# PotDiv1_v4.net
KiCad netlist of a schematic drawn in EAGLE
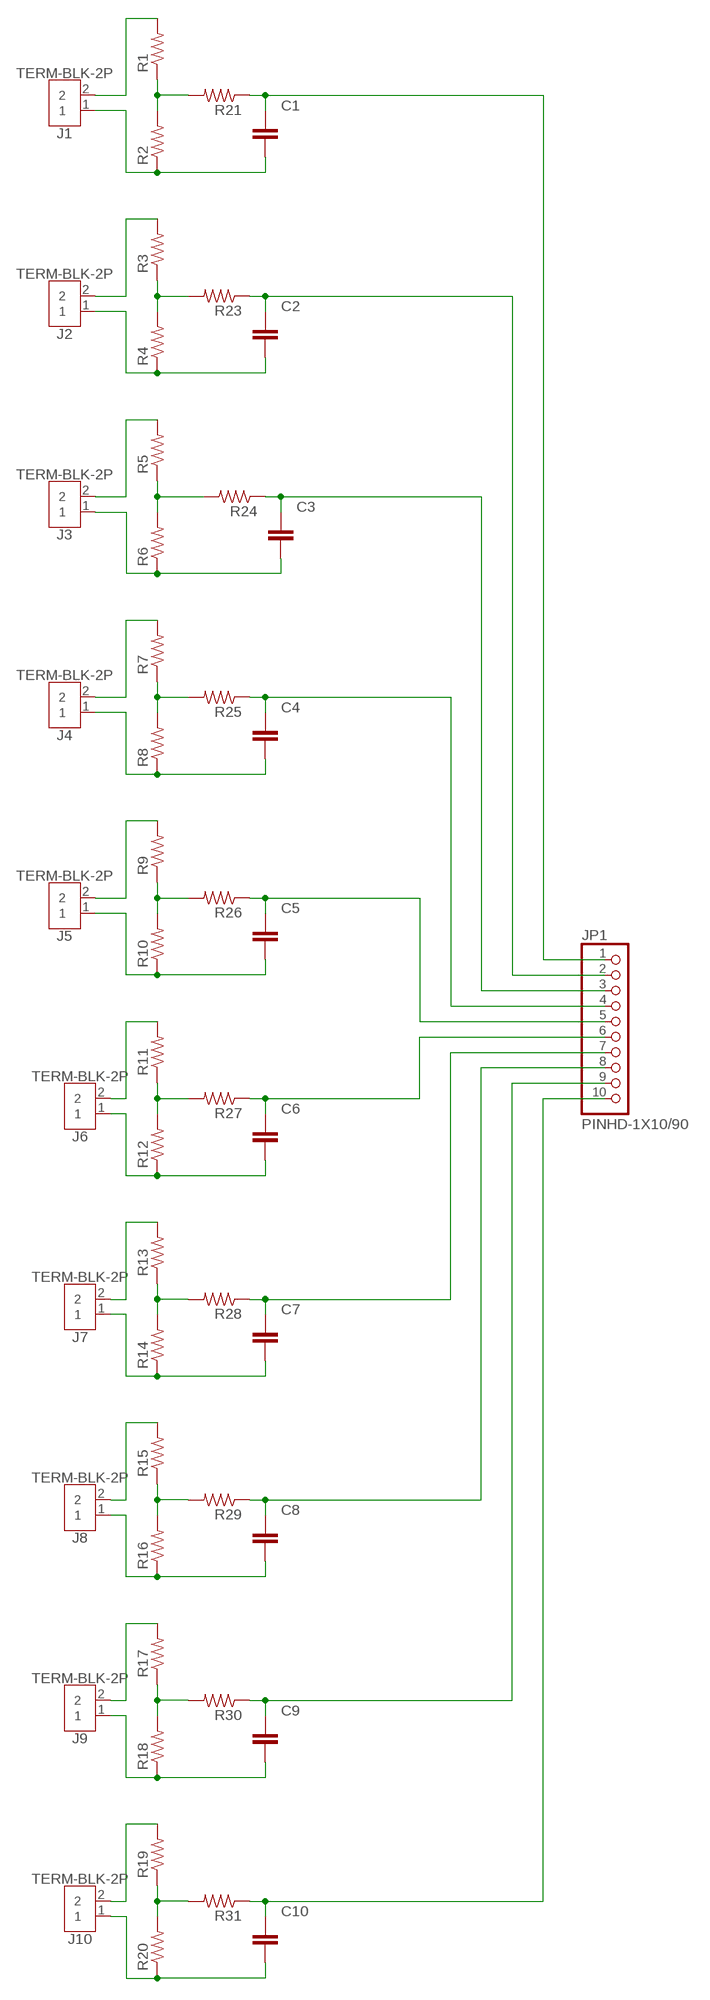
[diagram p0: schematic, sheet 1]

(export (version "E")
  (design (tool "Eeschema 10.0.6"))
  (components
    (comp (ref "C1")
      (value "C_RADIAL-12.5MM-DIA")
      (footprint "eagle-import:CAPRD550W60D1025H1250B")
      (libsource (lib "eagle-import") (part "CRADIAL-12.5MM-DIA_"))
    )
    (comp (ref "C2")
      (value "C_RADIAL-12.5MM-DIA")
      (footprint "eagle-import:CAPRD550W60D1025H1250B")
      (libsource (lib "eagle-import") (part "CRADIAL-12.5MM-DIA_"))
    )
    (comp (ref "C3")
      (value "C_RADIAL-12.5MM-DIA")
      (footprint "eagle-import:CAPRD550W60D1025H1250B")
      (libsource (lib "eagle-import") (part "CRADIAL-12.5MM-DIA_"))
    )
    (comp (ref "C4")
      (value "C_RADIAL-12.5MM-DIA")
      (footprint "eagle-import:CAPRD550W60D1025H1250B")
      (libsource (lib "eagle-import") (part "CRADIAL-12.5MM-DIA_"))
    )
    (comp (ref "C5")
      (value "C_RADIAL-12.5MM-DIA")
      (footprint "eagle-import:CAPRD550W60D1025H1250B")
      (libsource (lib "eagle-import") (part "CRADIAL-12.5MM-DIA_"))
    )
    (comp (ref "C6")
      (value "C_RADIAL-12.5MM-DIA")
      (footprint "eagle-import:CAPRD550W60D1025H1250B")
      (libsource (lib "eagle-import") (part "CRADIAL-12.5MM-DIA_"))
    )
    (comp (ref "C7")
      (value "C_RADIAL-12.5MM-DIA")
      (footprint "eagle-import:CAPRD550W60D1025H1250B")
      (libsource (lib "eagle-import") (part "CRADIAL-12.5MM-DIA_"))
    )
    (comp (ref "C8")
      (value "C_RADIAL-12.5MM-DIA")
      (footprint "eagle-import:CAPRD550W60D1025H1250B")
      (libsource (lib "eagle-import") (part "CRADIAL-12.5MM-DIA_"))
    )
    (comp (ref "C9")
      (value "C_RADIAL-12.5MM-DIA")
      (footprint "eagle-import:CAPRD550W60D1025H1250B")
      (libsource (lib "eagle-import") (part "CRADIAL-12.5MM-DIA_"))
    )
    (comp (ref "C10")
      (value "C_RADIAL-12.5MM-DIA")
      (footprint "eagle-import:CAPRD550W60D1025H1250B")
      (libsource (lib "eagle-import") (part "CRADIAL-12.5MM-DIA_"))
    )
    (comp (ref "J1")
      (value "TERM-BLK-2P")
      (footprint "eagle-import:TERMBLK_508-2N")
      (fields (field (name "MANUFACTURER") "TE Connectivity AMP Connectors") (field (name "MPN") "282837-2"))
      (libsource (lib "eagle-import") (part "2828XX-2282837-2"))
    )
    (comp (ref "J2")
      (value "TERM-BLK-2P")
      (footprint "eagle-import:TERMBLK_508-2N")
      (fields (field (name "MANUFACTURER") "TE Connectivity AMP Connectors") (field (name "MPN") "282837-2"))
      (libsource (lib "eagle-import") (part "2828XX-2282837-2"))
    )
    (comp (ref "J3")
      (value "TERM-BLK-2P")
      (footprint "eagle-import:TERMBLK_508-2N")
      (fields (field (name "MANUFACTURER") "TE Connectivity AMP Connectors") (field (name "MPN") "282837-2"))
      (libsource (lib "eagle-import") (part "2828XX-2282837-2"))
    )
    (comp (ref "J4")
      (value "TERM-BLK-2P")
      (footprint "eagle-import:TERMBLK_508-2N")
      (fields (field (name "MANUFACTURER") "TE Connectivity AMP Connectors") (field (name "MPN") "282837-2"))
      (libsource (lib "eagle-import") (part "2828XX-2282837-2"))
    )
    (comp (ref "J5")
      (value "TERM-BLK-2P")
      (footprint "eagle-import:TERMBLK_508-2N")
      (fields (field (name "MANUFACTURER") "TE Connectivity AMP Connectors") (field (name "MPN") "282837-2"))
      (libsource (lib "eagle-import") (part "2828XX-2282837-2"))
    )
    (comp (ref "J6")
      (value "TERM-BLK-2P")
      (footprint "eagle-import:TERMBLK_508-2N")
      (fields (field (name "MANUFACTURER") "TE Connectivity AMP Connectors") (field (name "MPN") "282837-2"))
      (libsource (lib "eagle-import") (part "2828XX-2282837-2"))
    )
    (comp (ref "J7")
      (value "TERM-BLK-2P")
      (footprint "eagle-import:TERMBLK_508-2N")
      (fields (field (name "MANUFACTURER") "TE Connectivity AMP Connectors") (field (name "MPN") "282837-2"))
      (libsource (lib "eagle-import") (part "2828XX-2282837-2"))
    )
    (comp (ref "J8")
      (value "TERM-BLK-2P")
      (footprint "eagle-import:TERMBLK_508-2N")
      (fields (field (name "MANUFACTURER") "TE Connectivity AMP Connectors") (field (name "MPN") "282837-2"))
      (libsource (lib "eagle-import") (part "2828XX-2282837-2"))
    )
    (comp (ref "J9")
      (value "TERM-BLK-2P")
      (footprint "eagle-import:TERMBLK_508-2N")
      (fields (field (name "MANUFACTURER") "TE Connectivity AMP Connectors") (field (name "MPN") "282837-2"))
      (libsource (lib "eagle-import") (part "2828XX-2282837-2"))
    )
    (comp (ref "J10")
      (value "TERM-BLK-2P")
      (footprint "eagle-import:TERMBLK_508-2N")
      (fields (field (name "MANUFACTURER") "TE Connectivity AMP Connectors") (field (name "MPN") "282837-2"))
      (libsource (lib "eagle-import") (part "2828XX-2282837-2"))
    )
    (comp (ref "JP1")
      (value "PINHD-1X10/90")
      (footprint "eagle-import:1X10_90")
      (fields (field (name "MANUFACTURER") "Generic"))
      (libsource (lib "eagle-import") (part "PINHD-1X10/90"))
    )
    (comp (ref "R1")
      (value "R-US_AXIAL-7.2MM-PITCH")
      (footprint "eagle-import:RESAD724W46L381D178B")
      (libsource (lib "eagle-import") (part "R-USAXIAL-7.2MM-PITCH_"))
    )
    (comp (ref "R2")
      (value "R-US_AXIAL-7.2MM-PITCH")
      (footprint "eagle-import:RESAD724W46L381D178B")
      (libsource (lib "eagle-import") (part "R-USAXIAL-7.2MM-PITCH_"))
    )
    (comp (ref "R3")
      (value "R-US_AXIAL-7.2MM-PITCH")
      (footprint "eagle-import:RESAD724W46L381D178B")
      (libsource (lib "eagle-import") (part "R-USAXIAL-7.2MM-PITCH_"))
    )
    (comp (ref "R4")
      (value "R-US_AXIAL-7.2MM-PITCH")
      (footprint "eagle-import:RESAD724W46L381D178B")
      (libsource (lib "eagle-import") (part "R-USAXIAL-7.2MM-PITCH_"))
    )
    (comp (ref "R5")
      (value "R-US_AXIAL-7.2MM-PITCH")
      (footprint "eagle-import:RESAD724W46L381D178B")
      (libsource (lib "eagle-import") (part "R-USAXIAL-7.2MM-PITCH_"))
    )
    (comp (ref "R6")
      (value "R-US_AXIAL-7.2MM-PITCH")
      (footprint "eagle-import:RESAD724W46L381D178B")
      (libsource (lib "eagle-import") (part "R-USAXIAL-7.2MM-PITCH_"))
    )
    (comp (ref "R7")
      (value "R-US_AXIAL-7.2MM-PITCH")
      (footprint "eagle-import:RESAD724W46L381D178B")
      (libsource (lib "eagle-import") (part "R-USAXIAL-7.2MM-PITCH_"))
    )
    (comp (ref "R8")
      (value "R-US_AXIAL-7.2MM-PITCH")
      (footprint "eagle-import:RESAD724W46L381D178B")
      (libsource (lib "eagle-import") (part "R-USAXIAL-7.2MM-PITCH_"))
    )
    (comp (ref "R9")
      (value "R-US_AXIAL-7.2MM-PITCH")
      (footprint "eagle-import:RESAD724W46L381D178B")
      (libsource (lib "eagle-import") (part "R-USAXIAL-7.2MM-PITCH_"))
    )
    (comp (ref "R10")
      (value "R-US_AXIAL-7.2MM-PITCH")
      (footprint "eagle-import:RESAD724W46L381D178B")
      (libsource (lib "eagle-import") (part "R-USAXIAL-7.2MM-PITCH_"))
    )
    (comp (ref "R11")
      (value "R-US_AXIAL-7.2MM-PITCH")
      (footprint "eagle-import:RESAD724W46L381D178B")
      (libsource (lib "eagle-import") (part "R-USAXIAL-7.2MM-PITCH_"))
    )
    (comp (ref "R12")
      (value "R-US_AXIAL-7.2MM-PITCH")
      (footprint "eagle-import:RESAD724W46L381D178B")
      (libsource (lib "eagle-import") (part "R-USAXIAL-7.2MM-PITCH_"))
    )
    (comp (ref "R13")
      (value "R-US_AXIAL-7.2MM-PITCH")
      (footprint "eagle-import:RESAD724W46L381D178B")
      (libsource (lib "eagle-import") (part "R-USAXIAL-7.2MM-PITCH_"))
    )
    (comp (ref "R14")
      (value "R-US_AXIAL-7.2MM-PITCH")
      (footprint "eagle-import:RESAD724W46L381D178B")
      (libsource (lib "eagle-import") (part "R-USAXIAL-7.2MM-PITCH_"))
    )
    (comp (ref "R15")
      (value "R-US_AXIAL-7.2MM-PITCH")
      (footprint "eagle-import:RESAD724W46L381D178B")
      (libsource (lib "eagle-import") (part "R-USAXIAL-7.2MM-PITCH_"))
    )
    (comp (ref "R16")
      (value "R-US_AXIAL-7.2MM-PITCH")
      (footprint "eagle-import:RESAD724W46L381D178B")
      (libsource (lib "eagle-import") (part "R-USAXIAL-7.2MM-PITCH_"))
    )
    (comp (ref "R17")
      (value "R-US_AXIAL-7.2MM-PITCH")
      (footprint "eagle-import:RESAD724W46L381D178B")
      (libsource (lib "eagle-import") (part "R-USAXIAL-7.2MM-PITCH_"))
    )
    (comp (ref "R18")
      (value "R-US_AXIAL-7.2MM-PITCH")
      (footprint "eagle-import:RESAD724W46L381D178B")
      (libsource (lib "eagle-import") (part "R-USAXIAL-7.2MM-PITCH_"))
    )
    (comp (ref "R19")
      (value "R-US_AXIAL-7.2MM-PITCH")
      (footprint "eagle-import:RESAD724W46L381D178B")
      (libsource (lib "eagle-import") (part "R-USAXIAL-7.2MM-PITCH_"))
    )
    (comp (ref "R20")
      (value "R-US_AXIAL-7.2MM-PITCH")
      (footprint "eagle-import:RESAD724W46L381D178B")
      (libsource (lib "eagle-import") (part "R-USAXIAL-7.2MM-PITCH_"))
    )
    (comp (ref "R21")
      (value "R-US_AXIAL-7.2MM-PITCH")
      (footprint "eagle-import:RESAD724W46L381D178B")
      (libsource (lib "eagle-import") (part "R-USAXIAL-7.2MM-PITCH_"))
    )
    (comp (ref "R23")
      (value "R-US_AXIAL-7.2MM-PITCH")
      (footprint "eagle-import:RESAD724W46L381D178B")
      (libsource (lib "eagle-import") (part "R-USAXIAL-7.2MM-PITCH_"))
    )
    (comp (ref "R24")
      (value "R-US_AXIAL-7.2MM-PITCH")
      (footprint "eagle-import:RESAD724W46L381D178B")
      (libsource (lib "eagle-import") (part "R-USAXIAL-7.2MM-PITCH_"))
    )
    (comp (ref "R25")
      (value "R-US_AXIAL-7.2MM-PITCH")
      (footprint "eagle-import:RESAD724W46L381D178B")
      (libsource (lib "eagle-import") (part "R-USAXIAL-7.2MM-PITCH_"))
    )
    (comp (ref "R26")
      (value "R-US_AXIAL-7.2MM-PITCH")
      (footprint "eagle-import:RESAD724W46L381D178B")
      (libsource (lib "eagle-import") (part "R-USAXIAL-7.2MM-PITCH_"))
    )
    (comp (ref "R27")
      (value "R-US_AXIAL-7.2MM-PITCH")
      (footprint "eagle-import:RESAD724W46L381D178B")
      (libsource (lib "eagle-import") (part "R-USAXIAL-7.2MM-PITCH_"))
    )
    (comp (ref "R28")
      (value "R-US_AXIAL-7.2MM-PITCH")
      (footprint "eagle-import:RESAD724W46L381D178B")
      (libsource (lib "eagle-import") (part "R-USAXIAL-7.2MM-PITCH_"))
    )
    (comp (ref "R29")
      (value "R-US_AXIAL-7.2MM-PITCH")
      (footprint "eagle-import:RESAD724W46L381D178B")
      (libsource (lib "eagle-import") (part "R-USAXIAL-7.2MM-PITCH_"))
    )
    (comp (ref "R30")
      (value "R-US_AXIAL-7.2MM-PITCH")
      (footprint "eagle-import:RESAD724W46L381D178B")
      (libsource (lib "eagle-import") (part "R-USAXIAL-7.2MM-PITCH_"))
    )
    (comp (ref "R31")
      (value "R-US_AXIAL-7.2MM-PITCH")
      (footprint "eagle-import:RESAD724W46L381D178B")
      (libsource (lib "eagle-import") (part "R-USAXIAL-7.2MM-PITCH_"))
    )
  )
  (nets
    (net (code "1") (name "Net-(C1-Pad1)") (class "Default")
      (node (ref "C1") (pin "1") (pinfunction "1_1") (pintype "passive"))
      (node (ref "JP1") (pin "1") (pinfunction "1_1") (pintype "passive"))
      (node (ref "R21") (pin "1") (pinfunction "1_1") (pintype "passive"))
    )
    (net (code "2") (name "Net-(C1-Pad2)") (class "Default")
      (node (ref "C1") (pin "2") (pinfunction "2_2") (pintype "passive"))
      (node (ref "J1") (pin "1") (pinfunction "1_1") (pintype "bidirectional"))
      (node (ref "R2") (pin "1") (pinfunction "1_1") (pintype "passive"))
    )
    (net (code "3") (name "Net-(C2-Pad1)") (class "Default")
      (node (ref "C2") (pin "1") (pinfunction "1_1") (pintype "passive"))
      (node (ref "JP1") (pin "2") (pinfunction "2_2") (pintype "passive"))
      (node (ref "R23") (pin "1") (pinfunction "1_1") (pintype "passive"))
    )
    (net (code "4") (name "Net-(C2-Pad2)") (class "Default")
      (node (ref "C2") (pin "2") (pinfunction "2_2") (pintype "passive"))
      (node (ref "J2") (pin "1") (pinfunction "1_1") (pintype "bidirectional"))
      (node (ref "R4") (pin "1") (pinfunction "1_1") (pintype "passive"))
    )
    (net (code "5") (name "Net-(C3-Pad1)") (class "Default")
      (node (ref "C3") (pin "1") (pinfunction "1_1") (pintype "passive"))
      (node (ref "JP1") (pin "3") (pinfunction "3_3") (pintype "passive"))
      (node (ref "R24") (pin "1") (pinfunction "1_1") (pintype "passive"))
    )
    (net (code "6") (name "Net-(C3-Pad2)") (class "Default")
      (node (ref "C3") (pin "2") (pinfunction "2_2") (pintype "passive"))
      (node (ref "J3") (pin "1") (pinfunction "1_1") (pintype "bidirectional"))
      (node (ref "R6") (pin "1") (pinfunction "1_1") (pintype "passive"))
    )
    (net (code "7") (name "Net-(C4-Pad1)") (class "Default")
      (node (ref "C4") (pin "1") (pinfunction "1_1") (pintype "passive"))
      (node (ref "JP1") (pin "4") (pinfunction "4_4") (pintype "passive"))
      (node (ref "R25") (pin "1") (pinfunction "1_1") (pintype "passive"))
    )
    (net (code "8") (name "Net-(C4-Pad2)") (class "Default")
      (node (ref "C4") (pin "2") (pinfunction "2_2") (pintype "passive"))
      (node (ref "J4") (pin "1") (pinfunction "1_1") (pintype "bidirectional"))
      (node (ref "R8") (pin "1") (pinfunction "1_1") (pintype "passive"))
    )
    (net (code "9") (name "Net-(C5-Pad1)") (class "Default")
      (node (ref "C5") (pin "1") (pinfunction "1_1") (pintype "passive"))
      (node (ref "JP1") (pin "5") (pinfunction "5_5") (pintype "passive"))
      (node (ref "R26") (pin "1") (pinfunction "1_1") (pintype "passive"))
    )
    (net (code "10") (name "Net-(C5-Pad2)") (class "Default")
      (node (ref "C5") (pin "2") (pinfunction "2_2") (pintype "passive"))
      (node (ref "J5") (pin "1") (pinfunction "1_1") (pintype "bidirectional"))
      (node (ref "R10") (pin "1") (pinfunction "1_1") (pintype "passive"))
    )
    (net (code "11") (name "Net-(C6-Pad1)") (class "Default")
      (node (ref "C6") (pin "1") (pinfunction "1_1") (pintype "passive"))
      (node (ref "JP1") (pin "6") (pinfunction "6_6") (pintype "passive"))
      (node (ref "R27") (pin "1") (pinfunction "1_1") (pintype "passive"))
    )
    (net (code "12") (name "Net-(C6-Pad2)") (class "Default")
      (node (ref "C6") (pin "2") (pinfunction "2_2") (pintype "passive"))
      (node (ref "J6") (pin "1") (pinfunction "1_1") (pintype "bidirectional"))
      (node (ref "R12") (pin "1") (pinfunction "1_1") (pintype "passive"))
    )
    (net (code "13") (name "Net-(C7-Pad1)") (class "Default")
      (node (ref "C7") (pin "1") (pinfunction "1_1") (pintype "passive"))
      (node (ref "JP1") (pin "7") (pinfunction "7_7") (pintype "passive"))
      (node (ref "R28") (pin "1") (pinfunction "1_1") (pintype "passive"))
    )
    (net (code "14") (name "Net-(C7-Pad2)") (class "Default")
      (node (ref "C7") (pin "2") (pinfunction "2_2") (pintype "passive"))
      (node (ref "J7") (pin "1") (pinfunction "1_1") (pintype "bidirectional"))
      (node (ref "R14") (pin "1") (pinfunction "1_1") (pintype "passive"))
    )
    (net (code "15") (name "Net-(C8-Pad1)") (class "Default")
      (node (ref "C8") (pin "1") (pinfunction "1_1") (pintype "passive"))
      (node (ref "JP1") (pin "8") (pinfunction "8_8") (pintype "passive"))
      (node (ref "R29") (pin "1") (pinfunction "1_1") (pintype "passive"))
    )
    (net (code "16") (name "Net-(C8-Pad2)") (class "Default")
      (node (ref "C8") (pin "2") (pinfunction "2_2") (pintype "passive"))
      (node (ref "J8") (pin "1") (pinfunction "1_1") (pintype "bidirectional"))
      (node (ref "R16") (pin "1") (pinfunction "1_1") (pintype "passive"))
    )
    (net (code "17") (name "Net-(C9-Pad1)") (class "Default")
      (node (ref "C9") (pin "1") (pinfunction "1_1") (pintype "passive"))
      (node (ref "JP1") (pin "9") (pinfunction "9_9") (pintype "passive"))
      (node (ref "R30") (pin "1") (pinfunction "1_1") (pintype "passive"))
    )
    (net (code "18") (name "Net-(C9-Pad2)") (class "Default")
      (node (ref "C9") (pin "2") (pinfunction "2_2") (pintype "passive"))
      (node (ref "J9") (pin "1") (pinfunction "1_1") (pintype "bidirectional"))
      (node (ref "R18") (pin "1") (pinfunction "1_1") (pintype "passive"))
    )
    (net (code "19") (name "Net-(C10-Pad1)") (class "Default")
      (node (ref "C10") (pin "1") (pinfunction "1_1") (pintype "passive"))
      (node (ref "JP1") (pin "10") (pinfunction "10_10") (pintype "passive"))
      (node (ref "R31") (pin "1") (pinfunction "1_1") (pintype "passive"))
    )
    (net (code "20") (name "Net-(C10-Pad2)") (class "Default")
      (node (ref "C10") (pin "2") (pinfunction "2_2") (pintype "passive"))
      (node (ref "J10") (pin "1") (pinfunction "1_1") (pintype "bidirectional"))
      (node (ref "R20") (pin "1") (pinfunction "1_1") (pintype "passive"))
    )
    (net (code "21") (name "Net-(J1-Pad2)") (class "Default")
      (node (ref "J1") (pin "2") (pinfunction "2_2") (pintype "bidirectional"))
      (node (ref "R1") (pin "2") (pinfunction "2_2") (pintype "passive"))
    )
    (net (code "22") (name "Net-(J2-Pad2)") (class "Default")
      (node (ref "J2") (pin "2") (pinfunction "2_2") (pintype "bidirectional"))
      (node (ref "R3") (pin "2") (pinfunction "2_2") (pintype "passive"))
    )
    (net (code "23") (name "Net-(J3-Pad2)") (class "Default")
      (node (ref "J3") (pin "2") (pinfunction "2_2") (pintype "bidirectional"))
      (node (ref "R5") (pin "2") (pinfunction "2_2") (pintype "passive"))
    )
    (net (code "24") (name "Net-(J4-Pad2)") (class "Default")
      (node (ref "J4") (pin "2") (pinfunction "2_2") (pintype "bidirectional"))
      (node (ref "R7") (pin "2") (pinfunction "2_2") (pintype "passive"))
    )
    (net (code "25") (name "Net-(J5-Pad2)") (class "Default")
      (node (ref "J5") (pin "2") (pinfunction "2_2") (pintype "bidirectional"))
      (node (ref "R9") (pin "2") (pinfunction "2_2") (pintype "passive"))
    )
    (net (code "26") (name "Net-(J6-Pad2)") (class "Default")
      (node (ref "J6") (pin "2") (pinfunction "2_2") (pintype "bidirectional"))
      (node (ref "R11") (pin "2") (pinfunction "2_2") (pintype "passive"))
    )
    (net (code "27") (name "Net-(J7-Pad2)") (class "Default")
      (node (ref "J7") (pin "2") (pinfunction "2_2") (pintype "bidirectional"))
      (node (ref "R13") (pin "2") (pinfunction "2_2") (pintype "passive"))
    )
    (net (code "28") (name "Net-(J8-Pad2)") (class "Default")
      (node (ref "J8") (pin "2") (pinfunction "2_2") (pintype "bidirectional"))
      (node (ref "R15") (pin "2") (pinfunction "2_2") (pintype "passive"))
    )
    (net (code "29") (name "Net-(J9-Pad2)") (class "Default")
      (node (ref "J9") (pin "2") (pinfunction "2_2") (pintype "bidirectional"))
      (node (ref "R17") (pin "2") (pinfunction "2_2") (pintype "passive"))
    )
    (net (code "30") (name "Net-(J10-Pad2)") (class "Default")
      (node (ref "J10") (pin "2") (pinfunction "2_2") (pintype "bidirectional"))
      (node (ref "R19") (pin "2") (pinfunction "2_2") (pintype "passive"))
    )
    (net (code "31") (name "Net-(R1-Pad1)") (class "Default")
      (node (ref "R1") (pin "1") (pinfunction "1_1") (pintype "passive"))
      (node (ref "R2") (pin "2") (pinfunction "2_2") (pintype "passive"))
      (node (ref "R21") (pin "2") (pinfunction "2_2") (pintype "passive"))
    )
    (net (code "32") (name "Net-(R10-Pad2)") (class "Default")
      (node (ref "R10") (pin "2") (pinfunction "2_2") (pintype "passive"))
      (node (ref "R26") (pin "2") (pinfunction "2_2") (pintype "passive"))
      (node (ref "R9") (pin "1") (pinfunction "1_1") (pintype "passive"))
    )
    (net (code "33") (name "Net-(R11-Pad1)") (class "Default")
      (node (ref "R11") (pin "1") (pinfunction "1_1") (pintype "passive"))
      (node (ref "R12") (pin "2") (pinfunction "2_2") (pintype "passive"))
      (node (ref "R27") (pin "2") (pinfunction "2_2") (pintype "passive"))
    )
    (net (code "34") (name "Net-(R13-Pad1)") (class "Default")
      (node (ref "R13") (pin "1") (pinfunction "1_1") (pintype "passive"))
      (node (ref "R14") (pin "2") (pinfunction "2_2") (pintype "passive"))
      (node (ref "R28") (pin "2") (pinfunction "2_2") (pintype "passive"))
    )
    (net (code "35") (name "Net-(R15-Pad1)") (class "Default")
      (node (ref "R15") (pin "1") (pinfunction "1_1") (pintype "passive"))
      (node (ref "R16") (pin "2") (pinfunction "2_2") (pintype "passive"))
      (node (ref "R29") (pin "2") (pinfunction "2_2") (pintype "passive"))
    )
    (net (code "36") (name "Net-(R17-Pad1)") (class "Default")
      (node (ref "R17") (pin "1") (pinfunction "1_1") (pintype "passive"))
      (node (ref "R18") (pin "2") (pinfunction "2_2") (pintype "passive"))
      (node (ref "R30") (pin "2") (pinfunction "2_2") (pintype "passive"))
    )
    (net (code "37") (name "Net-(R19-Pad1)") (class "Default")
      (node (ref "R19") (pin "1") (pinfunction "1_1") (pintype "passive"))
      (node (ref "R20") (pin "2") (pinfunction "2_2") (pintype "passive"))
      (node (ref "R31") (pin "2") (pinfunction "2_2") (pintype "passive"))
    )
    (net (code "38") (name "Net-(R23-Pad2)") (class "Default")
      (node (ref "R23") (pin "2") (pinfunction "2_2") (pintype "passive"))
      (node (ref "R3") (pin "1") (pinfunction "1_1") (pintype "passive"))
      (node (ref "R4") (pin "2") (pinfunction "2_2") (pintype "passive"))
    )
    (net (code "39") (name "Net-(R24-Pad2)") (class "Default")
      (node (ref "R24") (pin "2") (pinfunction "2_2") (pintype "passive"))
      (node (ref "R5") (pin "1") (pinfunction "1_1") (pintype "passive"))
      (node (ref "R6") (pin "2") (pinfunction "2_2") (pintype "passive"))
    )
    (net (code "40") (name "Net-(R25-Pad2)") (class "Default")
      (node (ref "R25") (pin "2") (pinfunction "2_2") (pintype "passive"))
      (node (ref "R7") (pin "1") (pinfunction "1_1") (pintype "passive"))
      (node (ref "R8") (pin "2") (pinfunction "2_2") (pintype "passive"))
    )
  )
)
